# h_bridge.net
KiCad netlist of a schematic drawn in EAGLE
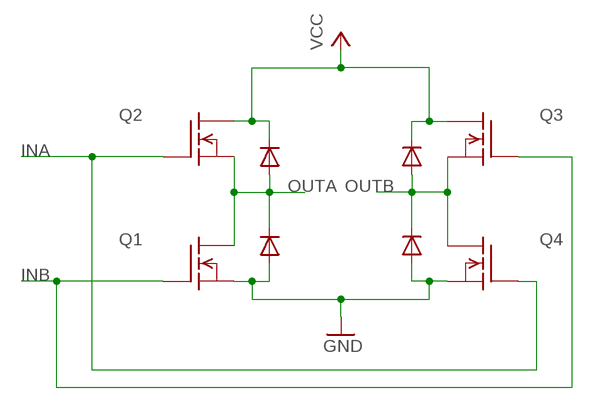
[diagram p0: schematic, sheet 1]

(export (version "E")
  (design (tool "Eeschema 10.0.6"))
  (components
    (comp (ref "Q1")
      (value "BSS97")
      (footprint "eagle-import:TO202")
      (libsource (lib "eagle-import") (part "BSS97"))
    )
    (comp (ref "Q2")
      (value "BSS97")
      (footprint "eagle-import:TO202")
      (libsource (lib "eagle-import") (part "BSS97"))
    )
    (comp (ref "Q3")
      (value "BSS97")
      (footprint "eagle-import:TO202")
      (libsource (lib "eagle-import") (part "BSS97"))
    )
    (comp (ref "Q4")
      (value "BSS97")
      (footprint "eagle-import:TO202")
      (libsource (lib "eagle-import") (part "BSS97"))
    )
  )
  (nets
    (net (code "1") (name "/INA") (class "Default")
      (node (ref "Q2") (pin "3") (pinfunction "G_3") (pintype "passive"))
      (node (ref "Q4") (pin "3") (pinfunction "G_3") (pintype "passive"))
    )
    (net (code "2") (name "/INB") (class "Default")
      (node (ref "Q1") (pin "3") (pinfunction "G_3") (pintype "passive"))
      (node (ref "Q3") (pin "3") (pinfunction "G_3") (pintype "passive"))
    )
    (net (code "3") (name "/OUTA") (class "Default")
      (node (ref "Q1") (pin "2") (pinfunction "D_2") (pintype "passive"))
      (node (ref "Q2") (pin "1") (pinfunction "S_1") (pintype "passive"))
    )
    (net (code "4") (name "/OUTB") (class "Default")
      (node (ref "Q3") (pin "1") (pinfunction "S_1") (pintype "passive"))
      (node (ref "Q4") (pin "2") (pinfunction "D_2") (pintype "passive"))
    )
    (net (code "5") (name "GND") (class "Default")
      (node (ref "Q1") (pin "1") (pinfunction "S_1") (pintype "passive"))
      (node (ref "Q4") (pin "1") (pinfunction "S_1") (pintype "passive"))
    )
    (net (code "6") (name "VCC") (class "Default")
      (node (ref "Q2") (pin "2") (pinfunction "D_2") (pintype "passive"))
      (node (ref "Q3") (pin "2") (pinfunction "D_2") (pintype "passive"))
    )
  )
)
